# warmwhite_strip_x5.net
KiCad netlist of a schematic drawn in EAGLE
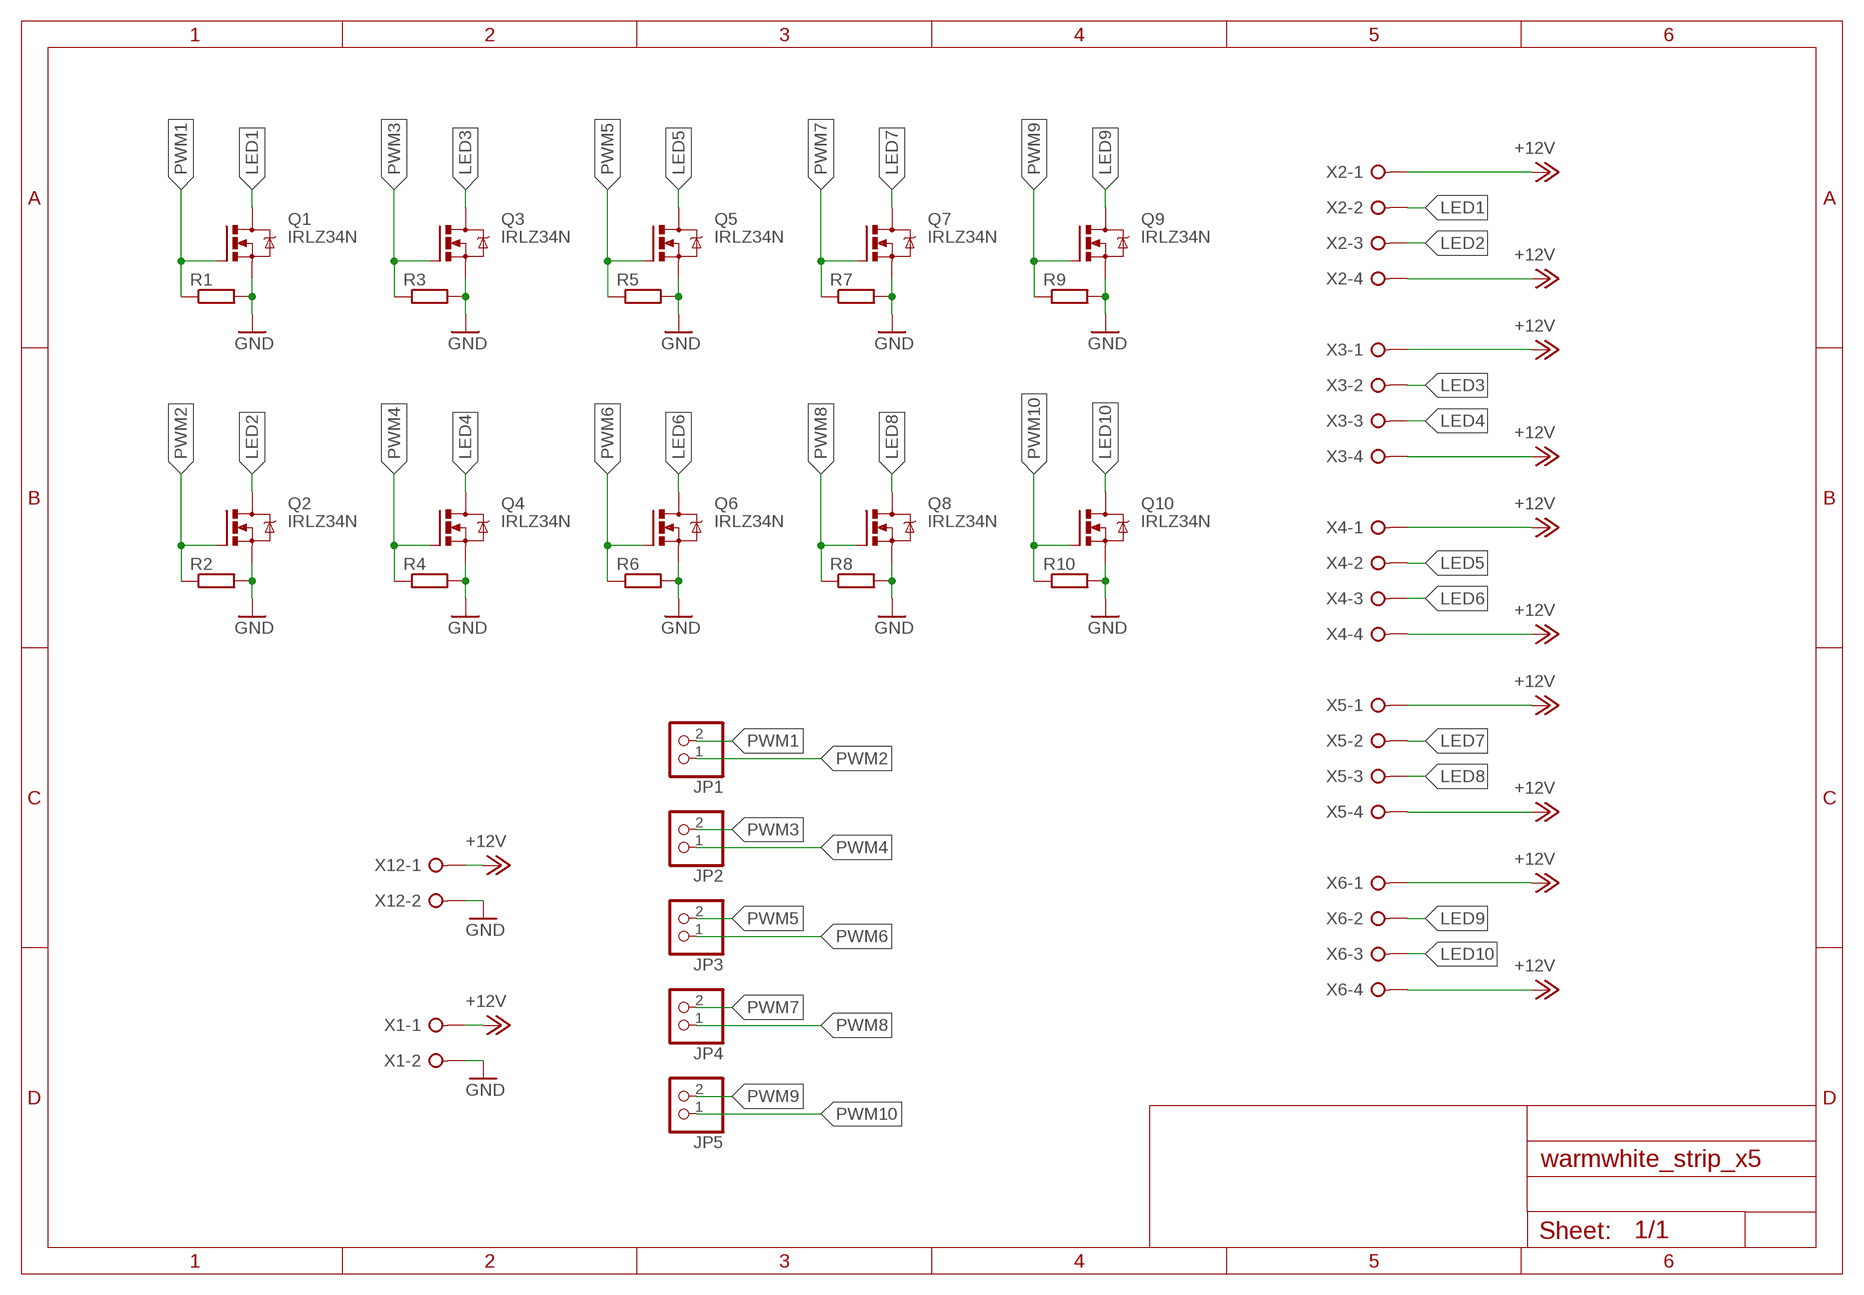
[diagram p0: schematic, sheet 1]

(export (version "E")
  (design (tool "Eeschema 10.0.6"))
  (components
    (comp (ref "JP1")
      (value "PINHD-1X2")
      (footprint "eagle-import:1X02")
      (libsource (lib "eagle-import") (part "PINHD-1X2"))
    )
    (comp (ref "JP2")
      (value "PINHD-1X2")
      (footprint "eagle-import:1X02")
      (libsource (lib "eagle-import") (part "PINHD-1X2"))
    )
    (comp (ref "JP3")
      (value "PINHD-1X2")
      (footprint "eagle-import:1X02")
      (libsource (lib "eagle-import") (part "PINHD-1X2"))
    )
    (comp (ref "JP4")
      (value "PINHD-1X2")
      (footprint "eagle-import:1X02")
      (libsource (lib "eagle-import") (part "PINHD-1X2"))
    )
    (comp (ref "JP5")
      (value "PINHD-1X2")
      (footprint "eagle-import:1X02")
      (libsource (lib "eagle-import") (part "PINHD-1X2"))
    )
    (comp (ref "Q1")
      (value "IRLZ34N")
      (footprint "eagle-import:TO220BV")
      (libsource (lib "eagle-import") (part "IRLZ44ZTO220BV"))
    )
    (comp (ref "Q2")
      (value "IRLZ34N")
      (footprint "eagle-import:TO220BV")
      (libsource (lib "eagle-import") (part "IRLZ44ZTO220BV"))
    )
    (comp (ref "Q3")
      (value "IRLZ34N")
      (footprint "eagle-import:TO220BV")
      (libsource (lib "eagle-import") (part "IRLZ44ZTO220BV"))
    )
    (comp (ref "Q4")
      (value "IRLZ34N")
      (footprint "eagle-import:TO220BV")
      (libsource (lib "eagle-import") (part "IRLZ44ZTO220BV"))
    )
    (comp (ref "Q5")
      (value "IRLZ34N")
      (footprint "eagle-import:TO220BV")
      (libsource (lib "eagle-import") (part "IRLZ44ZTO220BV"))
    )
    (comp (ref "Q6")
      (value "IRLZ34N")
      (footprint "eagle-import:TO220BV")
      (libsource (lib "eagle-import") (part "IRLZ44ZTO220BV"))
    )
    (comp (ref "Q7")
      (value "IRLZ34N")
      (footprint "eagle-import:TO220BV")
      (libsource (lib "eagle-import") (part "IRLZ44ZTO220BV"))
    )
    (comp (ref "Q8")
      (value "IRLZ34N")
      (footprint "eagle-import:TO220BV")
      (libsource (lib "eagle-import") (part "IRLZ44ZTO220BV"))
    )
    (comp (ref "Q9")
      (value "IRLZ34N")
      (footprint "eagle-import:TO220BV")
      (libsource (lib "eagle-import") (part "IRLZ44ZTO220BV"))
    )
    (comp (ref "Q10")
      (value "IRLZ34N")
      (footprint "eagle-import:TO220BV")
      (libsource (lib "eagle-import") (part "IRLZ44ZTO220BV"))
    )
    (comp (ref "R1")
      (value "R-EU_0207/10")
      (footprint "eagle-import:0207_10")
      (libsource (lib "eagle-import") (part "R-EU_0207/10"))
    )
    (comp (ref "R2")
      (value "R-EU_0207/10")
      (footprint "eagle-import:0207_10")
      (libsource (lib "eagle-import") (part "R-EU_0207/10"))
    )
    (comp (ref "R3")
      (value "R-EU_0207/10")
      (footprint "eagle-import:0207_10")
      (libsource (lib "eagle-import") (part "R-EU_0207/10"))
    )
    (comp (ref "R4")
      (value "R-EU_0207/10")
      (footprint "eagle-import:0207_10")
      (libsource (lib "eagle-import") (part "R-EU_0207/10"))
    )
    (comp (ref "R5")
      (value "R-EU_0207/10")
      (footprint "eagle-import:0207_10")
      (libsource (lib "eagle-import") (part "R-EU_0207/10"))
    )
    (comp (ref "R6")
      (value "R-EU_0207/10")
      (footprint "eagle-import:0207_10")
      (libsource (lib "eagle-import") (part "R-EU_0207/10"))
    )
    (comp (ref "R7")
      (value "R-EU_0207/10")
      (footprint "eagle-import:0207_10")
      (libsource (lib "eagle-import") (part "R-EU_0207/10"))
    )
    (comp (ref "R8")
      (value "R-EU_0207/10")
      (footprint "eagle-import:0207_10")
      (libsource (lib "eagle-import") (part "R-EU_0207/10"))
    )
    (comp (ref "R9")
      (value "R-EU_0207/10")
      (footprint "eagle-import:0207_10")
      (libsource (lib "eagle-import") (part "R-EU_0207/10"))
    )
    (comp (ref "R10")
      (value "R-EU_0207/10")
      (footprint "eagle-import:0207_10")
      (libsource (lib "eagle-import") (part "R-EU_0207/10"))
    )
    (comp (ref "X1")
      (value "W237-02P")
      (footprint "eagle-import:W237-132")
      (libsource (lib "eagle-import") (part "W237-02P"))
    )
    (comp (ref "X2")
      (value "W237-04P")
      (footprint "eagle-import:W237-4P")
      (libsource (lib "eagle-import") (part "W237-04P"))
    )
    (comp (ref "X3")
      (value "W237-04P")
      (footprint "eagle-import:W237-4P")
      (libsource (lib "eagle-import") (part "W237-04P"))
    )
    (comp (ref "X4")
      (value "W237-04P")
      (footprint "eagle-import:W237-4P")
      (libsource (lib "eagle-import") (part "W237-04P"))
    )
    (comp (ref "X5")
      (value "W237-04P")
      (footprint "eagle-import:W237-4P")
      (libsource (lib "eagle-import") (part "W237-04P"))
    )
    (comp (ref "X6")
      (value "W237-04P")
      (footprint "eagle-import:W237-4P")
      (libsource (lib "eagle-import") (part "W237-04P"))
    )
    (comp (ref "X12")
      (value "W237-02P")
      (footprint "eagle-import:W237-132")
      (libsource (lib "eagle-import") (part "W237-02P"))
    )
  )
  (nets
    (net (code "1") (name "+12V") (class "Default")
      (node (ref "X1") (pin "1") (pinfunction "KL_1") (pintype "passive"))
      (node (ref "X12") (pin "1") (pinfunction "KL_1") (pintype "passive"))
      (node (ref "X2") (pin "1") (pinfunction "KL_1") (pintype "passive"))
      (node (ref "X2") (pin "4") (pinfunction "KL_4") (pintype "passive"))
      (node (ref "X3") (pin "1") (pinfunction "KL_1") (pintype "passive"))
      (node (ref "X3") (pin "4") (pinfunction "KL_4") (pintype "passive"))
      (node (ref "X4") (pin "1") (pinfunction "KL_1") (pintype "passive"))
      (node (ref "X4") (pin "4") (pinfunction "KL_4") (pintype "passive"))
      (node (ref "X5") (pin "1") (pinfunction "KL_1") (pintype "passive"))
      (node (ref "X5") (pin "4") (pinfunction "KL_4") (pintype "passive"))
      (node (ref "X6") (pin "1") (pinfunction "KL_1") (pintype "passive"))
      (node (ref "X6") (pin "4") (pinfunction "KL_4") (pintype "passive"))
    )
    (net (code "2") (name "GND") (class "Default")
      (node (ref "Q1") (pin "S") (pinfunction "S_S") (pintype "passive"))
      (node (ref "Q10") (pin "S") (pinfunction "S_S") (pintype "passive"))
      (node (ref "Q2") (pin "S") (pinfunction "S_S") (pintype "passive"))
      (node (ref "Q3") (pin "S") (pinfunction "S_S") (pintype "passive"))
      (node (ref "Q4") (pin "S") (pinfunction "S_S") (pintype "passive"))
      (node (ref "Q5") (pin "S") (pinfunction "S_S") (pintype "passive"))
      (node (ref "Q6") (pin "S") (pinfunction "S_S") (pintype "passive"))
      (node (ref "Q7") (pin "S") (pinfunction "S_S") (pintype "passive"))
      (node (ref "Q8") (pin "S") (pinfunction "S_S") (pintype "passive"))
      (node (ref "Q9") (pin "S") (pinfunction "S_S") (pintype "passive"))
      (node (ref "R1") (pin "2") (pinfunction "2_2") (pintype "passive"))
      (node (ref "R10") (pin "2") (pinfunction "2_2") (pintype "passive"))
      (node (ref "R2") (pin "2") (pinfunction "2_2") (pintype "passive"))
      (node (ref "R3") (pin "2") (pinfunction "2_2") (pintype "passive"))
      (node (ref "R4") (pin "2") (pinfunction "2_2") (pintype "passive"))
      (node (ref "R5") (pin "2") (pinfunction "2_2") (pintype "passive"))
      (node (ref "R6") (pin "2") (pinfunction "2_2") (pintype "passive"))
      (node (ref "R7") (pin "2") (pinfunction "2_2") (pintype "passive"))
      (node (ref "R8") (pin "2") (pinfunction "2_2") (pintype "passive"))
      (node (ref "R9") (pin "2") (pinfunction "2_2") (pintype "passive"))
      (node (ref "X1") (pin "2") (pinfunction "KL_2") (pintype "passive"))
      (node (ref "X12") (pin "2") (pinfunction "KL_2") (pintype "passive"))
    )
    (net (code "3") (name "LED1") (class "Default")
      (node (ref "Q1") (pin "D") (pinfunction "D_D") (pintype "passive"))
      (node (ref "X2") (pin "2") (pinfunction "KL_2") (pintype "passive"))
    )
    (net (code "4") (name "LED2") (class "Default")
      (node (ref "Q2") (pin "D") (pinfunction "D_D") (pintype "passive"))
      (node (ref "X2") (pin "3") (pinfunction "KL_3") (pintype "passive"))
    )
    (net (code "5") (name "LED3") (class "Default")
      (node (ref "Q3") (pin "D") (pinfunction "D_D") (pintype "passive"))
      (node (ref "X3") (pin "2") (pinfunction "KL_2") (pintype "passive"))
    )
    (net (code "6") (name "LED4") (class "Default")
      (node (ref "Q4") (pin "D") (pinfunction "D_D") (pintype "passive"))
      (node (ref "X3") (pin "3") (pinfunction "KL_3") (pintype "passive"))
    )
    (net (code "7") (name "LED5") (class "Default")
      (node (ref "Q5") (pin "D") (pinfunction "D_D") (pintype "passive"))
      (node (ref "X4") (pin "2") (pinfunction "KL_2") (pintype "passive"))
    )
    (net (code "8") (name "LED6") (class "Default")
      (node (ref "Q6") (pin "D") (pinfunction "D_D") (pintype "passive"))
      (node (ref "X4") (pin "3") (pinfunction "KL_3") (pintype "passive"))
    )
    (net (code "9") (name "LED7") (class "Default")
      (node (ref "Q7") (pin "D") (pinfunction "D_D") (pintype "passive"))
      (node (ref "X5") (pin "2") (pinfunction "KL_2") (pintype "passive"))
    )
    (net (code "10") (name "LED8") (class "Default")
      (node (ref "Q8") (pin "D") (pinfunction "D_D") (pintype "passive"))
      (node (ref "X5") (pin "3") (pinfunction "KL_3") (pintype "passive"))
    )
    (net (code "11") (name "LED9") (class "Default")
      (node (ref "Q9") (pin "D") (pinfunction "D_D") (pintype "passive"))
      (node (ref "X6") (pin "2") (pinfunction "KL_2") (pintype "passive"))
    )
    (net (code "12") (name "LED10") (class "Default")
      (node (ref "Q10") (pin "D") (pinfunction "D_D") (pintype "passive"))
      (node (ref "X6") (pin "3") (pinfunction "KL_3") (pintype "passive"))
    )
    (net (code "13") (name "PWM1") (class "Default")
      (node (ref "JP1") (pin "2") (pinfunction "2_2") (pintype "passive"))
      (node (ref "Q1") (pin "G") (pinfunction "G_G") (pintype "passive"))
      (node (ref "R1") (pin "1") (pinfunction "1_1") (pintype "passive"))
    )
    (net (code "14") (name "PWM2") (class "Default")
      (node (ref "JP1") (pin "1") (pinfunction "1_1") (pintype "passive"))
      (node (ref "Q2") (pin "G") (pinfunction "G_G") (pintype "passive"))
      (node (ref "R2") (pin "1") (pinfunction "1_1") (pintype "passive"))
    )
    (net (code "15") (name "PWM3") (class "Default")
      (node (ref "JP2") (pin "2") (pinfunction "2_2") (pintype "passive"))
      (node (ref "Q3") (pin "G") (pinfunction "G_G") (pintype "passive"))
      (node (ref "R3") (pin "1") (pinfunction "1_1") (pintype "passive"))
    )
    (net (code "16") (name "PWM4") (class "Default")
      (node (ref "JP2") (pin "1") (pinfunction "1_1") (pintype "passive"))
      (node (ref "Q4") (pin "G") (pinfunction "G_G") (pintype "passive"))
      (node (ref "R4") (pin "1") (pinfunction "1_1") (pintype "passive"))
    )
    (net (code "17") (name "PWM5") (class "Default")
      (node (ref "JP3") (pin "2") (pinfunction "2_2") (pintype "passive"))
      (node (ref "Q5") (pin "G") (pinfunction "G_G") (pintype "passive"))
      (node (ref "R5") (pin "1") (pinfunction "1_1") (pintype "passive"))
    )
    (net (code "18") (name "PWM6") (class "Default")
      (node (ref "JP3") (pin "1") (pinfunction "1_1") (pintype "passive"))
      (node (ref "Q6") (pin "G") (pinfunction "G_G") (pintype "passive"))
      (node (ref "R6") (pin "1") (pinfunction "1_1") (pintype "passive"))
    )
    (net (code "19") (name "PWM7") (class "Default")
      (node (ref "JP4") (pin "2") (pinfunction "2_2") (pintype "passive"))
      (node (ref "Q7") (pin "G") (pinfunction "G_G") (pintype "passive"))
      (node (ref "R7") (pin "1") (pinfunction "1_1") (pintype "passive"))
    )
    (net (code "20") (name "PWM8") (class "Default")
      (node (ref "JP4") (pin "1") (pinfunction "1_1") (pintype "passive"))
      (node (ref "Q8") (pin "G") (pinfunction "G_G") (pintype "passive"))
      (node (ref "R8") (pin "1") (pinfunction "1_1") (pintype "passive"))
    )
    (net (code "21") (name "PWM9") (class "Default")
      (node (ref "JP5") (pin "2") (pinfunction "2_2") (pintype "passive"))
      (node (ref "Q9") (pin "G") (pinfunction "G_G") (pintype "passive"))
      (node (ref "R9") (pin "1") (pinfunction "1_1") (pintype "passive"))
    )
    (net (code "22") (name "PWM10") (class "Default")
      (node (ref "JP5") (pin "1") (pinfunction "1_1") (pintype "passive"))
      (node (ref "Q10") (pin "G") (pinfunction "G_G") (pintype "passive"))
      (node (ref "R10") (pin "1") (pinfunction "1_1") (pintype "passive"))
    )
  )
)
